# SOT-23-8-SOIC-8-Adapter.net
KiCad netlist of a schematic drawn in EAGLE
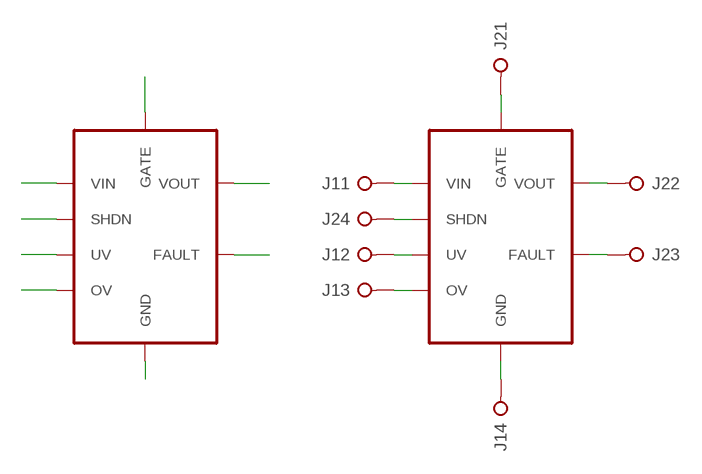
[diagram p0: schematic, sheet 1]

(export (version "E")
  (design (tool "Eeschema 10.0.6"))
  (components
    (comp (ref "J1")
      (value "PINHD-1X4")
      (footprint "eagle-import:1X04")
      (libsource (lib "eagle-import") (part "PINHD-1X4"))
    )
    (comp (ref "J2")
      (value "PINHD-1X4")
      (footprint "eagle-import:1X04")
      (libsource (lib "eagle-import") (part "PINHD-1X4"))
    )
    (comp (ref "Q1")
      (value "LTC4365")
      (footprint "eagle-import:SOT-23-8")
      (libsource (lib "eagle-import") (part "LTC4365"))
    )
    (comp (ref "U$1")
      (value "DUMMY1")
      (footprint "eagle-import:SOIC-08")
      (libsource (lib "eagle-import") (part "DUMMY1"))
    )
  )
  (nets
    (net (code "1") (name "/1-1") (class "Default")
      (node (ref "J1") (pin "1") (pinfunction "KL_1") (pintype "passive"))
      (node (ref "Q1") (pin "1") (pinfunction "VIN_1") (pintype "power_in"))
      (node (ref "U$1") (pin "1") (pinfunction "VIN_1") (pintype "power_in"))
    )
    (net (code "2") (name "/1-2") (class "Default")
      (node (ref "J1") (pin "2") (pinfunction "KL_2") (pintype "passive"))
      (node (ref "Q1") (pin "2") (pinfunction "UV_2") (pintype "input"))
      (node (ref "U$1") (pin "2") (pinfunction "UV_2") (pintype "input"))
    )
    (net (code "3") (name "/1-3") (class "Default")
      (node (ref "J1") (pin "3") (pinfunction "KL_3") (pintype "passive"))
      (node (ref "Q1") (pin "3") (pinfunction "OV_3") (pintype "input"))
      (node (ref "U$1") (pin "3") (pinfunction "OV_3") (pintype "input"))
    )
    (net (code "4") (name "/1-4") (class "Default")
      (node (ref "J1") (pin "4") (pinfunction "KL_4") (pintype "passive"))
      (node (ref "Q1") (pin "4") (pinfunction "GND_4") (pintype "passive"))
      (node (ref "U$1") (pin "4") (pinfunction "GND_4") (pintype "passive"))
    )
    (net (code "5") (name "/2-1") (class "Default")
      (node (ref "J2") (pin "1") (pinfunction "KL_1") (pintype "passive"))
      (node (ref "Q1") (pin "8") (pinfunction "GATE_8") (pintype "output"))
      (node (ref "U$1") (pin "8") (pinfunction "GATE_8") (pintype "output"))
    )
    (net (code "6") (name "/2-2") (class "Default")
      (node (ref "J2") (pin "2") (pinfunction "KL_2") (pintype "passive"))
      (node (ref "Q1") (pin "7") (pinfunction "VOUT_7") (pintype "input"))
      (node (ref "U$1") (pin "7") (pinfunction "VOUT_7") (pintype "input"))
    )
    (net (code "7") (name "/2-3") (class "Default")
      (node (ref "J2") (pin "3") (pinfunction "KL_3") (pintype "passive"))
      (node (ref "Q1") (pin "6") (pinfunction "FAULT_6") (pintype "output"))
      (node (ref "U$1") (pin "6") (pinfunction "FAULT_6") (pintype "output"))
    )
    (net (code "8") (name "/2-4") (class "Default")
      (node (ref "J2") (pin "4") (pinfunction "KL_4") (pintype "passive"))
      (node (ref "Q1") (pin "5") (pinfunction "SHDN_5") (pintype "input"))
      (node (ref "U$1") (pin "5") (pinfunction "SHDN_5") (pintype "input"))
    )
  )
)
